# 3V3_REG.net
KiCad netlist of a schematic drawn in Altium Designer
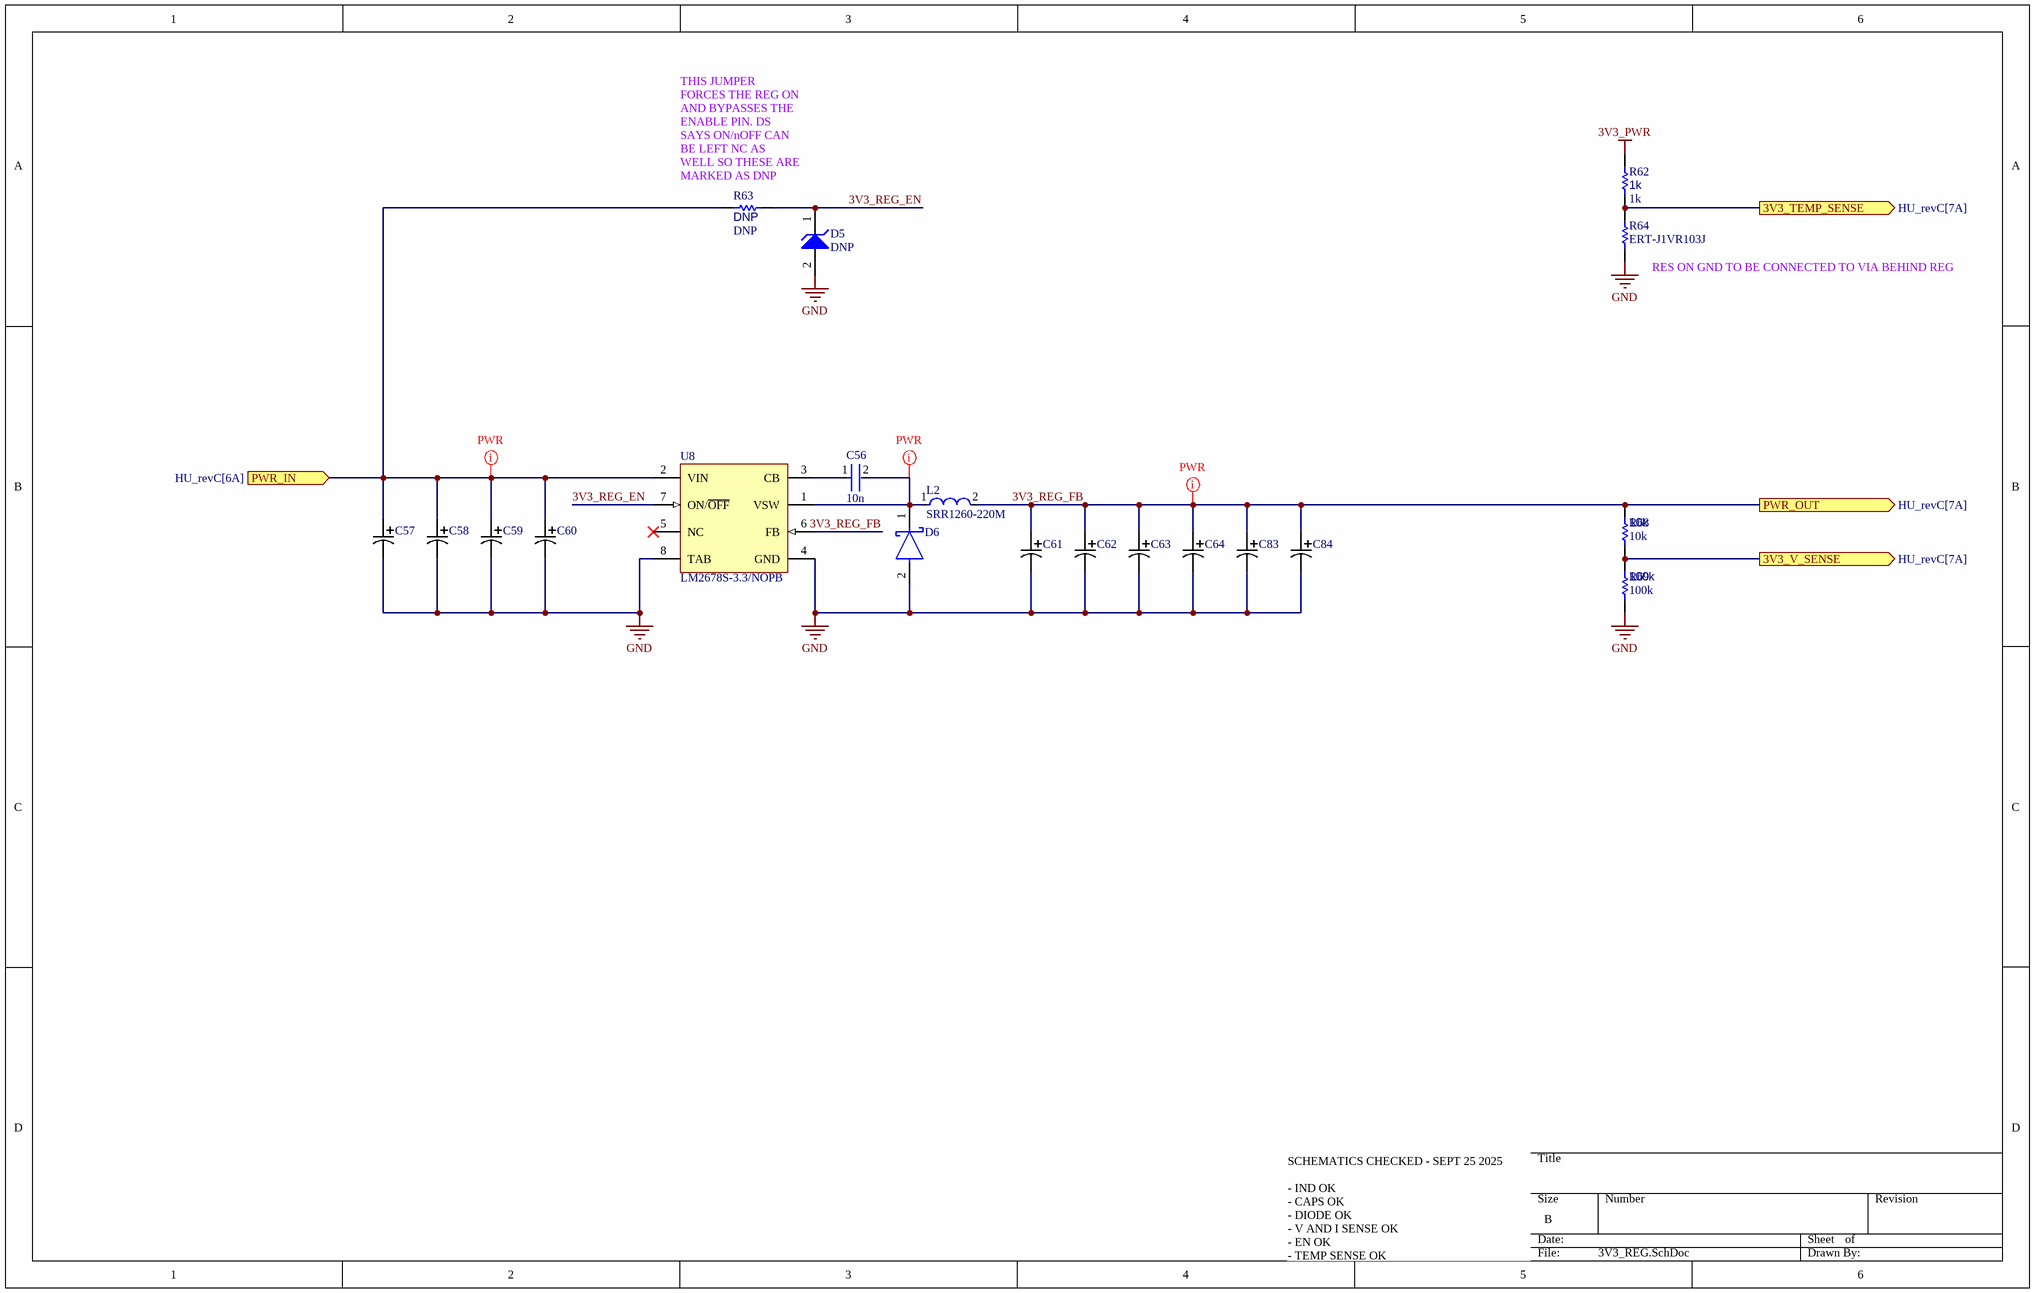
[diagram p0: 3V3_REG.SchDoc]

(export (version "E")
  (design (tool "Eeschema 10.0.6"))
  (components
    (comp (ref "C56")
      (value "10n")
      (footprint "FP-0402-L_1_0_0_05-W_0_5-IPC_A")
      (description "LARGE PADS, 0402 CAP, CHANGE COMMENT TO MATCH REAL P/N")
      (libsource (lib "Space Concordia") (part "b4654b650e69147ec39a6b967a45e02"))
    )
    (comp (ref "C57")
      (value "T495D475K050ATE300")
      (footprint "T495D475K050ATE300-Footprint-1")
      (description "Cap Tant Solid 4.7uF 50V D CASE 10% (7.3 X 4.3 X 2.8mm) SMD 7343-31 0.3 Ohm 125 C T/R")
      (fields (field (name "TOLERANCE") "10%"))
      (libsource (lib "Space Concordia") (part "T495D475K050ATE300"))
    )
    (comp (ref "C58")
      (value "T495D475K050ATE300")
      (footprint "T495D475K050ATE300-Footprint-1")
      (description "Cap Tant Solid 4.7uF 50V D CASE 10% (7.3 X 4.3 X 2.8mm) SMD 7343-31 0.3 Ohm 125 C T/R")
      (fields (field (name "TOLERANCE") "10%"))
      (libsource (lib "Space Concordia") (part "T495D475K050ATE300"))
    )
    (comp (ref "C59")
      (value "T495D475K050ATE300")
      (footprint "T495D475K050ATE300-Footprint-1")
      (description "Cap Tant Solid 4.7uF 50V D CASE 10% (7.3 X 4.3 X 2.8mm) SMD 7343-31 0.3 Ohm 125 C T/R")
      (fields (field (name "TOLERANCE") "10%"))
      (libsource (lib "Space Concordia") (part "T495D475K050ATE300"))
    )
    (comp (ref "C60")
      (value "T495D475K050ATE300")
      (footprint "T495D475K050ATE300-Footprint-1")
      (description "Cap Tant Solid 4.7uF 50V D CASE 10% (7.3 X 4.3 X 2.8mm) SMD 7343-31 0.3 Ohm 125 C T/R")
      (fields (field (name "TOLERANCE") "10%"))
      (libsource (lib "Space Concordia") (part "T495D475K050ATE300"))
    )
    (comp (ref "C61")
      (value "T495X107K020ATE150")
      (footprint "T495D337K010ATE150-Footprint-1")
      (description "T495X107K020ATE150 diff p/n")
      (fields (field (name "TOLERANCE") "10%"))
      (libsource (lib "Space Concordia") (part "T495D337K010ATE150"))
    )
    (comp (ref "C62")
      (value "T495X107K020ATE150")
      (footprint "T495D337K010ATE150-Footprint-1")
      (description "T495X107K020ATE150 diff p/n")
      (fields (field (name "TOLERANCE") "10%"))
      (libsource (lib "Space Concordia") (part "T495D337K010ATE150"))
    )
    (comp (ref "C63")
      (value "T495X107K020ATE150")
      (footprint "T495D337K010ATE150-Footprint-1")
      (description "T495X107K020ATE150 diff p/n")
      (fields (field (name "TOLERANCE") "10%"))
      (libsource (lib "Space Concordia") (part "T495D337K010ATE150"))
    )
    (comp (ref "C64")
      (value "DNP")
      (footprint "T495D337K010ATE150-Footprint-1")
      (fields (field (name "TOLERANCE") "10%"))
      (libsource (lib "Space Concordia") (part "T495D337K010ATE150"))
    )
    (comp (ref "C83")
      (value "DNP")
      (footprint "T495D337K010ATE150-Footprint-1")
      (description "T495X107K020ATE150 diff p/n")
      (fields (field (name "TOLERANCE") "10%"))
      (libsource (lib "Space Concordia") (part "T495D337K010ATE150"))
    )
    (comp (ref "C84")
      (value "DNP")
      (footprint "T495D337K010ATE150-Footprint-1")
      (fields (field (name "TOLERANCE") "10%"))
      (libsource (lib "Space Concordia") (part "T495D337K010ATE150"))
    )
    (comp (ref "D5")
      (value "DNP")
      (footprint "ONSC-SOD-523-2-502-01_V")
      (description "Zener Voltage Regulator, 500 mW, 2-Pin SOD-523, Pb-Free, Tape and Reel")
      (fields (field (name "MANUFACTURER") "On Semiconductor") (field (name "PARTNUMBER") "MM5Z3V3T1G"))
      (libsource (lib "Altium Content Vault") (part "ONSC-K1A2-2"))
    )
    (comp (ref "D6")
      (value "B540C-13-F")
      (footprint "FP-SMC-MFG")
      (description "DIODE SCHOTTKY 40V 5A SMC")
      (fields
        (field (name "OCTOPART") "https://octopart.com/b540c-13-f-diodes+inc.-325873")
        (field (name "MANUFACTURER") "Diodes Inc.")
      )
      (libsource (lib "Altium Content Vault") (part "1d6ec82d83fb6aee721767c19dac4b9"))
    )
    (comp (ref "L2")
      (value "SRR1260-220M")
      (footprint "FP-SRR1260-MFG")
      (description "DIFF P/N: SRR1260-220M\r\n\r\nFIXED IND 22UH 5A 27 MOHM SMD")
      (fields (field (name "TOLERANCE") "20%"))
      (libsource (lib "Altium Content Vault") (part "725321dda6339637d4d059423bc1c3c"))
    )
    (comp (ref "R62")
      (value "1k")
      (footprint "R0603B")
      (description "Resistor")
      (fields (field (name "ALTIUM_VALUE") "1k"))
      (libsource (lib "Space Concordia") (part "Resistor"))
    )
    (comp (ref "R63")
      (value "DNP")
      (footprint "R0603B")
      (description "Resistor")
      (fields (field (name "ALTIUM_VALUE") "DNP"))
      (libsource (lib "Space Concordia") (part "Resistor"))
    )
    (comp (ref "R64")
      (value "ERT-J1VR103J")
      (footprint "RESC1608X90X30ML15T20")
      (fields (field (name "MANUFACTURER") "Panasonic"))
      (libsource (lib "Altium Content Vault") (part "RES"))
    )
    (comp (ref "R68")
      (value "10k")
      (footprint "R0603B")
      (description "Resistor")
      (fields (field (name "ALTIUM_VALUE") "10k"))
      (libsource (lib "Space Concordia") (part "Resistor"))
    )
    (comp (ref "R69")
      (value "100k")
      (footprint "R0603B")
      (description "Resistor")
      (fields (field (name "ALTIUM_VALUE") "100k"))
      (libsource (lib "Space Concordia") (part "Resistor"))
    )
    (comp (ref "U8")
      (value "LM2678S-3.3/NOPB")
      (footprint "KTW0007B_N")
      (description "SIMPLE SWITCHER® High Efficiency 5A Step-Down Voltage Regulator, 7-pin TO-263, Pb-Free")
      (fields (field (name "MANUFACTURER") "Texas Instruments"))
      (libsource (lib "Altium Content Vault") (part "PM-REG-LM2678S"))
    )
  )
  (nets
    (net (code "1") (name "/3V3_REG_EN") (class "Default")
      (node (ref "D5") (pin "1") (pinfunction "K_1") (pintype "passive"))
      (node (ref "R63") (pin "2") (pinfunction "2_2") (pintype "passive"))
      (node (ref "U8") (pin "7") (pinfunction "ON/~{OFF}_7") (pintype "input"))
    )
    (net (code "2") (name "/3V3_REG_FB") (class "Default")
      (node (ref "C61") (pin "1") (pinfunction "1_1") (pintype "passive"))
      (node (ref "C62") (pin "1") (pinfunction "1_1") (pintype "passive"))
      (node (ref "C63") (pin "1") (pinfunction "1_1") (pintype "passive"))
      (node (ref "C64") (pin "1") (pinfunction "1_1") (pintype "passive"))
      (node (ref "C83") (pin "1") (pinfunction "1_1") (pintype "passive"))
      (node (ref "C84") (pin "1") (pinfunction "1_1") (pintype "passive"))
      (node (ref "L2") (pin "2") (pinfunction "2_2") (pintype "passive"))
      (node (ref "R68") (pin "2") (pinfunction "2_2") (pintype "passive"))
      (node (ref "U8") (pin "6") (pinfunction "FB_6") (pintype "input"))
    )
    (net (code "3") (name "/3V3_TEMP_SENSE") (class "Default")
      (node (ref "R62") (pin "2") (pinfunction "2_2") (pintype "passive"))
      (node (ref "R64") (pin "2") (pinfunction "2_2") (pintype "passive"))
    )
    (net (code "4") (name "/3V3_V_SENSE") (class "Default")
      (node (ref "R68") (pin "1") (pinfunction "1_1") (pintype "passive"))
      (node (ref "R69") (pin "2") (pinfunction "2_2") (pintype "passive"))
    )
    (net (code "5") (name "/PWR_IN") (class "Default")
      (node (ref "C57") (pin "1") (pinfunction "1_1") (pintype "passive"))
      (node (ref "C58") (pin "1") (pinfunction "1_1") (pintype "passive"))
      (node (ref "C59") (pin "1") (pinfunction "1_1") (pintype "passive"))
      (node (ref "C60") (pin "1") (pinfunction "1_1") (pintype "passive"))
      (node (ref "R63") (pin "1") (pinfunction "1_1") (pintype "passive"))
      (node (ref "U8") (pin "2") (pinfunction "VIN_2") (pintype "power_in"))
    )
    (net (code "6") (name "3V3_PWR") (class "Default")
      (node (ref "R62") (pin "1") (pinfunction "1_1") (pintype "passive"))
    )
    (net (code "7") (name "GND") (class "Default")
      (node (ref "C57") (pin "2") (pinfunction "2_2") (pintype "passive"))
      (node (ref "C58") (pin "2") (pinfunction "2_2") (pintype "passive"))
      (node (ref "C59") (pin "2") (pinfunction "2_2") (pintype "passive"))
      (node (ref "C60") (pin "2") (pinfunction "2_2") (pintype "passive"))
      (node (ref "C61") (pin "2") (pinfunction "2_2") (pintype "passive"))
      (node (ref "C62") (pin "2") (pinfunction "2_2") (pintype "passive"))
      (node (ref "C63") (pin "2") (pinfunction "2_2") (pintype "passive"))
      (node (ref "C64") (pin "2") (pinfunction "2_2") (pintype "passive"))
      (node (ref "C83") (pin "2") (pinfunction "2_2") (pintype "passive"))
      (node (ref "C84") (pin "2") (pinfunction "2_2") (pintype "passive"))
      (node (ref "D5") (pin "2") (pinfunction "A_2") (pintype "passive"))
      (node (ref "D6") (pin "2") (pinfunction "A_2") (pintype "passive"))
      (node (ref "R64") (pin "1") (pinfunction "1_1") (pintype "passive"))
      (node (ref "R69") (pin "1") (pinfunction "1_1") (pintype "passive"))
      (node (ref "U8") (pin "4") (pinfunction "GND_4") (pintype "power_in"))
      (node (ref "U8") (pin "8") (pinfunction "TAB_8") (pintype "power_in"))
    )
    (net (code "8") (name "Net-(D6-C)") (class "Default")
      (node (ref "C56") (pin "2") (pinfunction "2_2") (pintype "passive"))
      (node (ref "D6") (pin "1") (pinfunction "C_1") (pintype "passive"))
      (node (ref "L2") (pin "1") (pinfunction "1_1") (pintype "passive"))
      (node (ref "U8") (pin "1") (pinfunction "VSW_1") (pintype "power_in"))
    )
    (net (code "9") (name "Net-(U8-CB)") (class "Default")
      (node (ref "C56") (pin "1") (pinfunction "1_1") (pintype "passive"))
      (node (ref "U8") (pin "3") (pinfunction "CB_3") (pintype "passive"))
    )
    (net (code "10") (name "unconnected-(U8-NC-Pad5)") (class "Default")
      (node (ref "U8") (pin "5") (pinfunction "NC_5") (pintype "passive+no_connect"))
    )
  )
)
